# DNVT.net
KiCad netlist of a schematic drawn in EAGLE
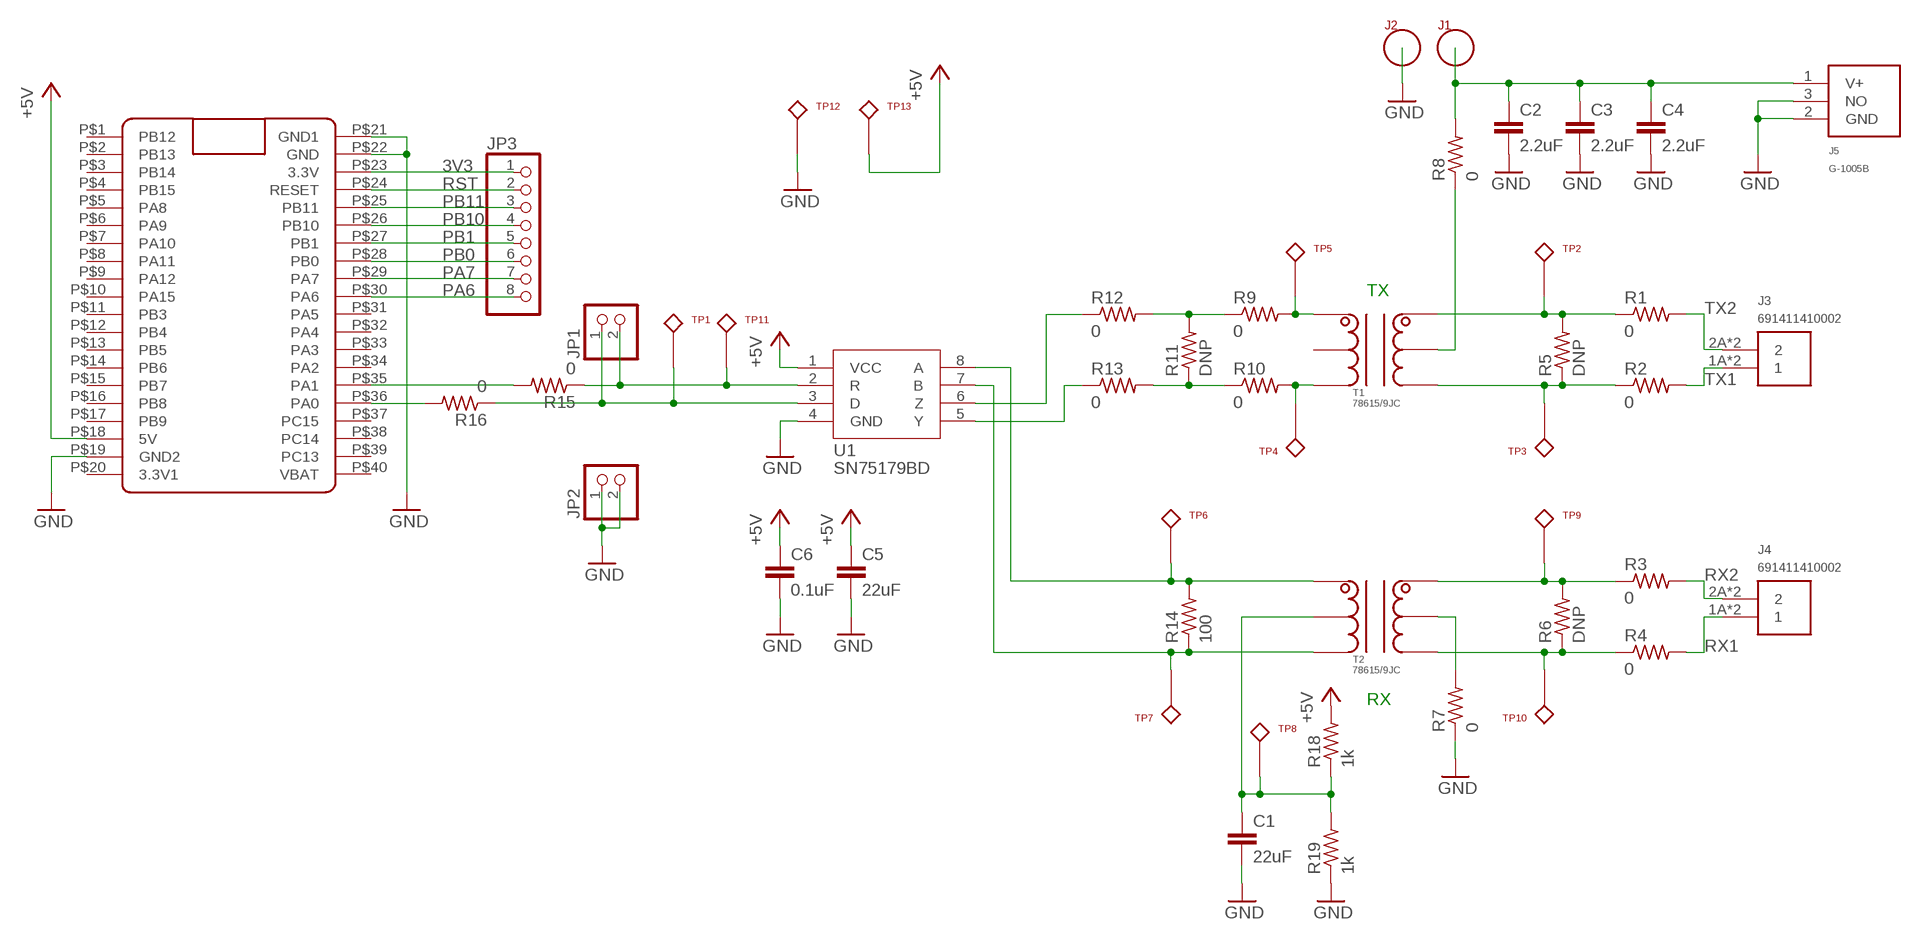
[diagram p0: schematic, sheet 1]

(export (version "E")
  (design (tool "Eeschema 10.0.6"))
  (components
    (comp (ref "C1")
      (value "22uF")
      (footprint "eagle-import:1210")
      (libsource (lib "eagle-import") (part "1210_CAPACITOR"))
    )
    (comp (ref "C2")
      (value "2.2uF")
      (footprint "eagle-import:1210")
      (libsource (lib "eagle-import") (part "1210_CAPACITOR"))
    )
    (comp (ref "C3")
      (value "2.2uF")
      (footprint "eagle-import:1210")
      (libsource (lib "eagle-import") (part "1210_CAPACITOR"))
    )
    (comp (ref "C4")
      (value "2.2uF")
      (footprint "eagle-import:1210")
      (libsource (lib "eagle-import") (part "1210_CAPACITOR"))
    )
    (comp (ref "C5")
      (value "22uF")
      (footprint "eagle-import:1210")
      (libsource (lib "eagle-import") (part "1210_CAPACITOR"))
    )
    (comp (ref "C6")
      (value "0.1uF")
      (footprint "eagle-import:0603")
      (libsource (lib "eagle-import") (part "0603_CAPACITOR"))
    )
    (comp (ref "J1")
      (value "BANANA")
      (footprint "eagle-import:BANANA")
      (fields (field (name "PARTNO") "36-575-4-ND"))
      (libsource (lib "eagle-import") (part "BANANA"))
    )
    (comp (ref "J2")
      (value "BANANA")
      (footprint "eagle-import:BANANA")
      (fields (field (name "PARTNO") "36-575-4-ND"))
      (libsource (lib "eagle-import") (part "BANANA"))
    )
    (comp (ref "J3")
      (value "691411410002")
      (footprint "eagle-import:691411410002")
      (fields (field (name "PARTNO") "732-11084-ND"))
      (libsource (lib "eagle-import") (part "691411410002"))
    )
    (comp (ref "J4")
      (value "691411410002")
      (footprint "eagle-import:691411410002")
      (fields (field (name "PARTNO") "732-11084-ND"))
      (libsource (lib "eagle-import") (part "691411410002"))
    )
    (comp (ref "J5")
      (value "G-1005B")
      (footprint "eagle-import:G-1005B")
      (fields (field (name "PARTNO") "1939-G-1005B-ND"))
      (libsource (lib "eagle-import") (part "G-1005B"))
    )
    (comp (ref "JP1")
      (value "PINHD-1X2")
      (footprint "eagle-import:1X02")
      (libsource (lib "eagle-import") (part "PINHD-1X2"))
    )
    (comp (ref "JP2")
      (value "PINHD-1X2")
      (footprint "eagle-import:1X02")
      (libsource (lib "eagle-import") (part "PINHD-1X2"))
    )
    (comp (ref "JP3")
      (value "PINHD-1X8")
      (footprint "eagle-import:1X08")
      (libsource (lib "eagle-import") (part "PINHD-1X8"))
    )
    (comp (ref "R1")
      (value "0")
      (footprint "eagle-import:R0805")
      (libsource (lib "eagle-import") (part "R-US_R0805"))
    )
    (comp (ref "R2")
      (value "0")
      (footprint "eagle-import:R0805")
      (libsource (lib "eagle-import") (part "R-US_R0805"))
    )
    (comp (ref "R3")
      (value "0")
      (footprint "eagle-import:R0805")
      (libsource (lib "eagle-import") (part "R-US_R0805"))
    )
    (comp (ref "R4")
      (value "0")
      (footprint "eagle-import:R0805")
      (libsource (lib "eagle-import") (part "R-US_R0805"))
    )
    (comp (ref "R5")
      (value "DNP")
      (footprint "eagle-import:R0805")
      (libsource (lib "eagle-import") (part "R-US_R0805"))
    )
    (comp (ref "R6")
      (value "DNP")
      (footprint "eagle-import:R0805")
      (libsource (lib "eagle-import") (part "R-US_R0805"))
    )
    (comp (ref "R7")
      (value "0")
      (footprint "eagle-import:R0805")
      (libsource (lib "eagle-import") (part "R-US_R0805"))
    )
    (comp (ref "R8")
      (value "0")
      (footprint "eagle-import:R0805")
      (libsource (lib "eagle-import") (part "R-US_R0805"))
    )
    (comp (ref "R9")
      (value "0")
      (footprint "eagle-import:R0805")
      (libsource (lib "eagle-import") (part "R-US_R0805"))
    )
    (comp (ref "R10")
      (value "0")
      (footprint "eagle-import:R0805")
      (libsource (lib "eagle-import") (part "R-US_R0805"))
    )
    (comp (ref "R11")
      (value "DNP")
      (footprint "eagle-import:R0805")
      (libsource (lib "eagle-import") (part "R-US_R0805"))
    )
    (comp (ref "R12")
      (value "0")
      (footprint "eagle-import:R0805")
      (libsource (lib "eagle-import") (part "R-US_R0805"))
    )
    (comp (ref "R13")
      (value "0")
      (footprint "eagle-import:R0805")
      (libsource (lib "eagle-import") (part "R-US_R0805"))
    )
    (comp (ref "R14")
      (value "100")
      (footprint "eagle-import:R0805")
      (libsource (lib "eagle-import") (part "R-US_R0805"))
    )
    (comp (ref "R15")
      (value "0")
      (footprint "eagle-import:0603")
      (libsource (lib "eagle-import") (part "0603_RESISTOR"))
    )
    (comp (ref "R16")
      (value "0")
      (footprint "eagle-import:0603")
      (libsource (lib "eagle-import") (part "0603_RESISTOR"))
    )
    (comp (ref "R18")
      (value "1k")
      (footprint "eagle-import:0603")
      (libsource (lib "eagle-import") (part "0603_RESISTOR"))
    )
    (comp (ref "R19")
      (value "1k")
      (footprint "eagle-import:0603")
      (libsource (lib "eagle-import") (part "0603_RESISTOR"))
    )
    (comp (ref "T1")
      (value "78615/9JC")
      (footprint "eagle-import:786")
      (fields (field (name "PARTNO") "811-2423-ND"))
      (libsource (lib "eagle-import") (part "78615/9JC"))
    )
    (comp (ref "T2")
      (value "78615/9JC")
      (footprint "eagle-import:786")
      (fields (field (name "PARTNO") "811-2423-ND"))
      (libsource (lib "eagle-import") (part "78615/9JC"))
    )
    (comp (ref "TP1")
      (value "5001")
      (footprint "eagle-import:5001")
      (fields (field (name "PARTNO") "36-5001-ND"))
      (libsource (lib "eagle-import") (part "5001"))
    )
    (comp (ref "TP2")
      (value "5002")
      (footprint "eagle-import:5001")
      (fields (field (name "PARTNO") "36-5002-ND"))
      (libsource (lib "eagle-import") (part "5002"))
    )
    (comp (ref "TP3")
      (value "5002")
      (footprint "eagle-import:5001")
      (fields (field (name "PARTNO") "36-5002-ND"))
      (libsource (lib "eagle-import") (part "5002"))
    )
    (comp (ref "TP4")
      (value "5002")
      (footprint "eagle-import:5001")
      (fields (field (name "PARTNO") "36-5002-ND"))
      (libsource (lib "eagle-import") (part "5002"))
    )
    (comp (ref "TP5")
      (value "5002")
      (footprint "eagle-import:5001")
      (fields (field (name "PARTNO") "36-5002-ND"))
      (libsource (lib "eagle-import") (part "5002"))
    )
    (comp (ref "TP6")
      (value "5002")
      (footprint "eagle-import:5001")
      (fields (field (name "PARTNO") "36-5002-ND"))
      (libsource (lib "eagle-import") (part "5002"))
    )
    (comp (ref "TP7")
      (value "5002")
      (footprint "eagle-import:5001")
      (fields (field (name "PARTNO") "36-5002-ND"))
      (libsource (lib "eagle-import") (part "5002"))
    )
    (comp (ref "TP8")
      (value "5002")
      (footprint "eagle-import:5001")
      (fields (field (name "PARTNO") "36-5002-ND"))
      (libsource (lib "eagle-import") (part "5002"))
    )
    (comp (ref "TP9")
      (value "5002")
      (footprint "eagle-import:5001")
      (fields (field (name "PARTNO") "36-5002-ND"))
      (libsource (lib "eagle-import") (part "5002"))
    )
    (comp (ref "TP10")
      (value "5002")
      (footprint "eagle-import:5001")
      (fields (field (name "PARTNO") "36-5002-ND"))
      (libsource (lib "eagle-import") (part "5002"))
    )
    (comp (ref "TP11")
      (value "5001")
      (footprint "eagle-import:5001")
      (fields (field (name "PARTNO") "36-5001-ND"))
      (libsource (lib "eagle-import") (part "5001"))
    )
    (comp (ref "TP12")
      (value "5001")
      (footprint "eagle-import:5001")
      (fields (field (name "PARTNO") "36-5001-ND"))
      (libsource (lib "eagle-import") (part "5001"))
    )
    (comp (ref "TP13")
      (value "5001")
      (footprint "eagle-import:5001")
      (fields (field (name "PARTNO") "36-5001-ND"))
      (libsource (lib "eagle-import") (part "5001"))
    )
    (comp (ref "U$1")
      (value "BLUE_PILL")
      (footprint "eagle-import:BLUE_PILL")
      (libsource (lib "eagle-import") (part "BLUE_PILL"))
    )
    (comp (ref "U1")
      (value "SN75179BD")
      (footprint "eagle-import:SOIC8")
      (fields (field (name "PARTNO") "296-6860-5-ND"))
      (libsource (lib "eagle-import") (part "SN75179BD"))
    )
  )
  (nets
    (net (code "1") (name "+5V") (class "Default")
      (node (ref "C5") (pin "1") (pinfunction "1_1") (pintype "passive"))
      (node (ref "C6") (pin "1") (pinfunction "1_1") (pintype "passive"))
      (node (ref "R18") (pin "2") (pinfunction "2_2") (pintype "passive"))
      (node (ref "TP13") (pin "P$1") (pinfunction "P$1_P$1") (pintype "bidirectional"))
      (node (ref "U$1") (pin "P$18") (pinfunction "5V_P$18") (pintype "bidirectional"))
      (node (ref "U1") (pin "1") (pinfunction "VCC_1") (pintype "bidirectional"))
    )
    (net (code "2") (name "/3V3") (class "Default")
      (node (ref "JP3") (pin "1") (pinfunction "1_1") (pintype "passive"))
      (node (ref "U$1") (pin "P$23") (pinfunction "3.3V_P$23") (pintype "bidirectional"))
    )
    (net (code "3") (name "/PA6") (class "Default")
      (node (ref "JP3") (pin "8") (pinfunction "8_8") (pintype "passive"))
      (node (ref "U$1") (pin "P$30") (pinfunction "PA6_P$30") (pintype "bidirectional"))
    )
    (net (code "4") (name "/PA7") (class "Default")
      (node (ref "JP3") (pin "7") (pinfunction "7_7") (pintype "passive"))
      (node (ref "U$1") (pin "P$29") (pinfunction "PA7_P$29") (pintype "bidirectional"))
    )
    (net (code "5") (name "/PB0") (class "Default")
      (node (ref "JP3") (pin "6") (pinfunction "6_6") (pintype "passive"))
      (node (ref "U$1") (pin "P$28") (pinfunction "PB0_P$28") (pintype "bidirectional"))
    )
    (net (code "6") (name "/PB1") (class "Default")
      (node (ref "JP3") (pin "5") (pinfunction "5_5") (pintype "passive"))
      (node (ref "U$1") (pin "P$27") (pinfunction "PB1_P$27") (pintype "bidirectional"))
    )
    (net (code "7") (name "/PB10") (class "Default")
      (node (ref "JP3") (pin "4") (pinfunction "4_4") (pintype "passive"))
      (node (ref "U$1") (pin "P$26") (pinfunction "PB10_P$26") (pintype "bidirectional"))
    )
    (net (code "8") (name "/PB11") (class "Default")
      (node (ref "JP3") (pin "3") (pinfunction "3_3") (pintype "passive"))
      (node (ref "U$1") (pin "P$25") (pinfunction "PB11_P$25") (pintype "bidirectional"))
    )
    (net (code "9") (name "/RST") (class "Default")
      (node (ref "JP3") (pin "2") (pinfunction "2_2") (pintype "passive"))
      (node (ref "U$1") (pin "P$24") (pinfunction "RESET_P$24") (pintype "bidirectional"))
    )
    (net (code "10") (name "/RX1") (class "Default")
      (node (ref "J4") (pin "1A") (pinfunction "1_1A") (pintype "bidirectional"))
      (node (ref "J4") (pin "1B") (pinfunction "1_1B") (pintype "bidirectional"))
      (node (ref "R4") (pin "2") (pinfunction "2_2") (pintype "passive"))
    )
    (net (code "11") (name "/RX2") (class "Default")
      (node (ref "J4") (pin "2A") (pinfunction "2_2A") (pintype "bidirectional"))
      (node (ref "J4") (pin "2B") (pinfunction "2_2B") (pintype "bidirectional"))
      (node (ref "R3") (pin "2") (pinfunction "2_2") (pintype "passive"))
    )
    (net (code "12") (name "/TX1") (class "Default")
      (node (ref "J3") (pin "1A") (pinfunction "1_1A") (pintype "bidirectional"))
      (node (ref "J3") (pin "1B") (pinfunction "1_1B") (pintype "bidirectional"))
      (node (ref "R2") (pin "2") (pinfunction "2_2") (pintype "passive"))
    )
    (net (code "13") (name "/TX2") (class "Default")
      (node (ref "J3") (pin "2A") (pinfunction "2_2A") (pintype "bidirectional"))
      (node (ref "J3") (pin "2B") (pinfunction "2_2B") (pintype "bidirectional"))
      (node (ref "R1") (pin "2") (pinfunction "2_2") (pintype "passive"))
    )
    (net (code "14") (name "GND") (class "Default")
      (node (ref "C1") (pin "2") (pinfunction "2_2") (pintype "passive"))
      (node (ref "C2") (pin "2") (pinfunction "2_2") (pintype "passive"))
      (node (ref "C3") (pin "2") (pinfunction "2_2") (pintype "passive"))
      (node (ref "C4") (pin "2") (pinfunction "2_2") (pintype "passive"))
      (node (ref "C5") (pin "2") (pinfunction "2_2") (pintype "passive"))
      (node (ref "C6") (pin "2") (pinfunction "2_2") (pintype "passive"))
      (node (ref "J2") (pin "P$1") (pinfunction "P$1_P$1") (pintype "bidirectional"))
      (node (ref "J5") (pin "2") (pinfunction "GND_2") (pintype "bidirectional"))
      (node (ref "J5") (pin "3") (pinfunction "NO_3") (pintype "bidirectional"))
      (node (ref "JP2") (pin "1") (pinfunction "1_1") (pintype "passive"))
      (node (ref "JP2") (pin "2") (pinfunction "2_2") (pintype "passive"))
      (node (ref "R19") (pin "1") (pinfunction "1_1") (pintype "passive"))
      (node (ref "R7") (pin "1") (pinfunction "1_1") (pintype "passive"))
      (node (ref "TP12") (pin "P$1") (pinfunction "P$1_P$1") (pintype "bidirectional"))
      (node (ref "U$1") (pin "P$19") (pinfunction "GND2_P$19") (pintype "bidirectional"))
      (node (ref "U$1") (pin "P$21") (pinfunction "GND1_P$21") (pintype "power_in"))
      (node (ref "U$1") (pin "P$22") (pinfunction "GND_P$22") (pintype "bidirectional"))
      (node (ref "U1") (pin "4") (pinfunction "GND_4") (pintype "bidirectional"))
    )
    (net (code "15") (name "Net-(C1-Pad1)") (class "Default")
      (node (ref "C1") (pin "1") (pinfunction "1_1") (pintype "passive"))
      (node (ref "R18") (pin "1") (pinfunction "1_1") (pintype "passive"))
      (node (ref "R19") (pin "2") (pinfunction "2_2") (pintype "passive"))
      (node (ref "T2") (pin "2") (pinfunction "2_2") (pintype "bidirectional"))
      (node (ref "TP8") (pin "P$1") (pinfunction "P$1_P$1") (pintype "bidirectional"))
    )
    (net (code "16") (name "Net-(J5-V+)") (class "Default")
      (node (ref "C2") (pin "1") (pinfunction "1_1") (pintype "passive"))
      (node (ref "C3") (pin "1") (pinfunction "1_1") (pintype "passive"))
      (node (ref "C4") (pin "1") (pinfunction "1_1") (pintype "passive"))
      (node (ref "J1") (pin "P$1") (pinfunction "P$1_P$1") (pintype "bidirectional"))
      (node (ref "J5") (pin "1") (pinfunction "V+_1") (pintype "bidirectional"))
      (node (ref "R8") (pin "2") (pinfunction "2_2") (pintype "passive"))
    )
    (net (code "17") (name "Net-(R1-Pad1)") (class "Default")
      (node (ref "R1") (pin "1") (pinfunction "1_1") (pintype "passive"))
      (node (ref "R5") (pin "2") (pinfunction "2_2") (pintype "passive"))
      (node (ref "T1") (pin "6") (pinfunction "6_6") (pintype "bidirectional"))
      (node (ref "TP2") (pin "P$1") (pinfunction "P$1_P$1") (pintype "bidirectional"))
    )
    (net (code "18") (name "Net-(R2-Pad1)") (class "Default")
      (node (ref "R2") (pin "1") (pinfunction "1_1") (pintype "passive"))
      (node (ref "R5") (pin "1") (pinfunction "1_1") (pintype "passive"))
      (node (ref "T1") (pin "4") (pinfunction "4_4") (pintype "bidirectional"))
      (node (ref "TP3") (pin "P$1") (pinfunction "P$1_P$1") (pintype "bidirectional"))
    )
    (net (code "19") (name "Net-(R3-Pad1)") (class "Default")
      (node (ref "R3") (pin "1") (pinfunction "1_1") (pintype "passive"))
      (node (ref "R6") (pin "2") (pinfunction "2_2") (pintype "passive"))
      (node (ref "T2") (pin "6") (pinfunction "6_6") (pintype "bidirectional"))
      (node (ref "TP9") (pin "P$1") (pinfunction "P$1_P$1") (pintype "bidirectional"))
    )
    (net (code "20") (name "Net-(R4-Pad1)") (class "Default")
      (node (ref "R4") (pin "1") (pinfunction "1_1") (pintype "passive"))
      (node (ref "R6") (pin "1") (pinfunction "1_1") (pintype "passive"))
      (node (ref "T2") (pin "4") (pinfunction "4_4") (pintype "bidirectional"))
      (node (ref "TP10") (pin "P$1") (pinfunction "P$1_P$1") (pintype "bidirectional"))
    )
    (net (code "21") (name "Net-(R7-Pad2)") (class "Default")
      (node (ref "R7") (pin "2") (pinfunction "2_2") (pintype "passive"))
      (node (ref "T2") (pin "5") (pinfunction "5_5") (pintype "bidirectional"))
    )
    (net (code "22") (name "Net-(R8-Pad1)") (class "Default")
      (node (ref "R8") (pin "1") (pinfunction "1_1") (pintype "passive"))
      (node (ref "T1") (pin "5") (pinfunction "5_5") (pintype "bidirectional"))
    )
    (net (code "23") (name "Net-(R9-Pad2)") (class "Default")
      (node (ref "R9") (pin "2") (pinfunction "2_2") (pintype "passive"))
      (node (ref "T1") (pin "1") (pinfunction "1_1") (pintype "bidirectional"))
      (node (ref "TP5") (pin "P$1") (pinfunction "P$1_P$1") (pintype "bidirectional"))
    )
    (net (code "24") (name "Net-(R10-Pad1)") (class "Default")
      (node (ref "R10") (pin "1") (pinfunction "1_1") (pintype "passive"))
      (node (ref "R11") (pin "1") (pinfunction "1_1") (pintype "passive"))
      (node (ref "R13") (pin "2") (pinfunction "2_2") (pintype "passive"))
    )
    (net (code "25") (name "Net-(R10-Pad2)") (class "Default")
      (node (ref "R10") (pin "2") (pinfunction "2_2") (pintype "passive"))
      (node (ref "T1") (pin "3") (pinfunction "3_3") (pintype "bidirectional"))
      (node (ref "TP4") (pin "P$1") (pinfunction "P$1_P$1") (pintype "bidirectional"))
    )
    (net (code "26") (name "Net-(R11-Pad2)") (class "Default")
      (node (ref "R11") (pin "2") (pinfunction "2_2") (pintype "passive"))
      (node (ref "R12") (pin "2") (pinfunction "2_2") (pintype "passive"))
      (node (ref "R9") (pin "1") (pinfunction "1_1") (pintype "passive"))
    )
    (net (code "27") (name "Net-(U$1-PA0)") (class "Default")
      (node (ref "R16") (pin "2") (pinfunction "2_2") (pintype "passive"))
      (node (ref "U$1") (pin "P$36") (pinfunction "PA0_P$36") (pintype "bidirectional"))
    )
    (net (code "28") (name "Net-(U$1-PA1)") (class "Default")
      (node (ref "R15") (pin "2") (pinfunction "2_2") (pintype "passive"))
      (node (ref "U$1") (pin "P$35") (pinfunction "PA1_P$35") (pintype "bidirectional"))
    )
    (net (code "29") (name "Net-(U1-A)") (class "Default")
      (node (ref "R14") (pin "2") (pinfunction "2_2") (pintype "passive"))
      (node (ref "T2") (pin "1") (pinfunction "1_1") (pintype "bidirectional"))
      (node (ref "TP6") (pin "P$1") (pinfunction "P$1_P$1") (pintype "bidirectional"))
      (node (ref "U1") (pin "8") (pinfunction "A_8") (pintype "bidirectional"))
    )
    (net (code "30") (name "Net-(U1-B)") (class "Default")
      (node (ref "R14") (pin "1") (pinfunction "1_1") (pintype "passive"))
      (node (ref "T2") (pin "3") (pinfunction "3_3") (pintype "bidirectional"))
      (node (ref "TP7") (pin "P$1") (pinfunction "P$1_P$1") (pintype "bidirectional"))
      (node (ref "U1") (pin "7") (pinfunction "B_7") (pintype "bidirectional"))
    )
    (net (code "31") (name "Net-(U1-D)") (class "Default")
      (node (ref "JP1") (pin "1") (pinfunction "1_1") (pintype "passive"))
      (node (ref "R16") (pin "1") (pinfunction "1_1") (pintype "passive"))
      (node (ref "TP1") (pin "P$1") (pinfunction "P$1_P$1") (pintype "bidirectional"))
      (node (ref "U1") (pin "3") (pinfunction "D_3") (pintype "bidirectional"))
    )
    (net (code "32") (name "Net-(U1-R)") (class "Default")
      (node (ref "JP1") (pin "2") (pinfunction "2_2") (pintype "passive"))
      (node (ref "R15") (pin "1") (pinfunction "1_1") (pintype "passive"))
      (node (ref "TP11") (pin "P$1") (pinfunction "P$1_P$1") (pintype "bidirectional"))
      (node (ref "U1") (pin "2") (pinfunction "R_2") (pintype "bidirectional"))
    )
    (net (code "33") (name "Net-(U1-Y)") (class "Default")
      (node (ref "R13") (pin "1") (pinfunction "1_1") (pintype "passive"))
      (node (ref "U1") (pin "5") (pinfunction "Y_5") (pintype "bidirectional"))
    )
    (net (code "34") (name "Net-(U1-Z)") (class "Default")
      (node (ref "R12") (pin "1") (pinfunction "1_1") (pintype "passive"))
      (node (ref "U1") (pin "6") (pinfunction "Z_6") (pintype "bidirectional"))
    )
    (net (code "35") (name "unconnected-(T1-Pad2)") (class "Default")
      (node (ref "T1") (pin "2") (pinfunction "2_2") (pintype "bidirectional"))
    )
    (net (code "36") (name "unconnected-(U$1-3.3V1-PadP$20)") (class "Default")
      (node (ref "U$1") (pin "P$20") (pinfunction "3.3V1_P$20") (pintype "bidirectional"))
    )
    (net (code "37") (name "unconnected-(U$1-PA2-PadP$34)") (class "Default")
      (node (ref "U$1") (pin "P$34") (pinfunction "PA2_P$34") (pintype "bidirectional"))
    )
    (net (code "38") (name "unconnected-(U$1-PA3-PadP$33)") (class "Default")
      (node (ref "U$1") (pin "P$33") (pinfunction "PA3_P$33") (pintype "bidirectional"))
    )
    (net (code "39") (name "unconnected-(U$1-PA4-PadP$32)") (class "Default")
      (node (ref "U$1") (pin "P$32") (pinfunction "PA4_P$32") (pintype "bidirectional"))
    )
    (net (code "40") (name "unconnected-(U$1-PA5-PadP$31)") (class "Default")
      (node (ref "U$1") (pin "P$31") (pinfunction "PA5_P$31") (pintype "bidirectional"))
    )
    (net (code "41") (name "unconnected-(U$1-PA8-PadP$5)") (class "Default")
      (node (ref "U$1") (pin "P$5") (pinfunction "PA8_P$5") (pintype "bidirectional"))
    )
    (net (code "42") (name "unconnected-(U$1-PA9-PadP$6)") (class "Default")
      (node (ref "U$1") (pin "P$6") (pinfunction "PA9_P$6") (pintype "bidirectional"))
    )
    (net (code "43") (name "unconnected-(U$1-PA10-PadP$7)") (class "Default")
      (node (ref "U$1") (pin "P$7") (pinfunction "PA10_P$7") (pintype "bidirectional"))
    )
    (net (code "44") (name "unconnected-(U$1-PA11-PadP$8)") (class "Default")
      (node (ref "U$1") (pin "P$8") (pinfunction "PA11_P$8") (pintype "bidirectional"))
    )
    (net (code "45") (name "unconnected-(U$1-PA12-PadP$9)") (class "Default")
      (node (ref "U$1") (pin "P$9") (pinfunction "PA12_P$9") (pintype "bidirectional"))
    )
    (net (code "46") (name "unconnected-(U$1-PA15-PadP$10)") (class "Default")
      (node (ref "U$1") (pin "P$10") (pinfunction "PA15_P$10") (pintype "bidirectional"))
    )
    (net (code "47") (name "unconnected-(U$1-PB3-PadP$11)") (class "Default")
      (node (ref "U$1") (pin "P$11") (pinfunction "PB3_P$11") (pintype "bidirectional"))
    )
    (net (code "48") (name "unconnected-(U$1-PB4-PadP$12)") (class "Default")
      (node (ref "U$1") (pin "P$12") (pinfunction "PB4_P$12") (pintype "bidirectional"))
    )
    (net (code "49") (name "unconnected-(U$1-PB5-PadP$13)") (class "Default")
      (node (ref "U$1") (pin "P$13") (pinfunction "PB5_P$13") (pintype "bidirectional"))
    )
    (net (code "50") (name "unconnected-(U$1-PB6-PadP$14)") (class "Default")
      (node (ref "U$1") (pin "P$14") (pinfunction "PB6_P$14") (pintype "bidirectional"))
    )
    (net (code "51") (name "unconnected-(U$1-PB7-PadP$15)") (class "Default")
      (node (ref "U$1") (pin "P$15") (pinfunction "PB7_P$15") (pintype "bidirectional"))
    )
    (net (code "52") (name "unconnected-(U$1-PB8-PadP$16)") (class "Default")
      (node (ref "U$1") (pin "P$16") (pinfunction "PB8_P$16") (pintype "bidirectional"))
    )
    (net (code "53") (name "unconnected-(U$1-PB9-PadP$17)") (class "Default")
      (node (ref "U$1") (pin "P$17") (pinfunction "PB9_P$17") (pintype "bidirectional"))
    )
    (net (code "54") (name "unconnected-(U$1-PB12-PadP$1)") (class "Default")
      (node (ref "U$1") (pin "P$1") (pinfunction "PB12_P$1") (pintype "bidirectional"))
    )
    (net (code "55") (name "unconnected-(U$1-PB13-PadP$2)") (class "Default")
      (node (ref "U$1") (pin "P$2") (pinfunction "PB13_P$2") (pintype "bidirectional"))
    )
    (net (code "56") (name "unconnected-(U$1-PB14-PadP$3)") (class "Default")
      (node (ref "U$1") (pin "P$3") (pinfunction "PB14_P$3") (pintype "bidirectional"))
    )
    (net (code "57") (name "unconnected-(U$1-PB15-PadP$4)") (class "Default")
      (node (ref "U$1") (pin "P$4") (pinfunction "PB15_P$4") (pintype "bidirectional"))
    )
    (net (code "58") (name "unconnected-(U$1-PC13-PadP$39)") (class "Default")
      (node (ref "U$1") (pin "P$39") (pinfunction "PC13_P$39") (pintype "bidirectional"))
    )
    (net (code "59") (name "unconnected-(U$1-PC14-PadP$38)") (class "Default")
      (node (ref "U$1") (pin "P$38") (pinfunction "PC14_P$38") (pintype "bidirectional"))
    )
    (net (code "60") (name "unconnected-(U$1-PC15-PadP$37)") (class "Default")
      (node (ref "U$1") (pin "P$37") (pinfunction "PC15_P$37") (pintype "bidirectional"))
    )
    (net (code "61") (name "unconnected-(U$1-VBAT-PadP$40)") (class "Default")
      (node (ref "U$1") (pin "P$40") (pinfunction "VBAT_P$40") (pintype "bidirectional"))
    )
  )
)
